# SHDN-S04-V00-ShutdownRelay.net
KiCad netlist of a schematic drawn in Altium Designer
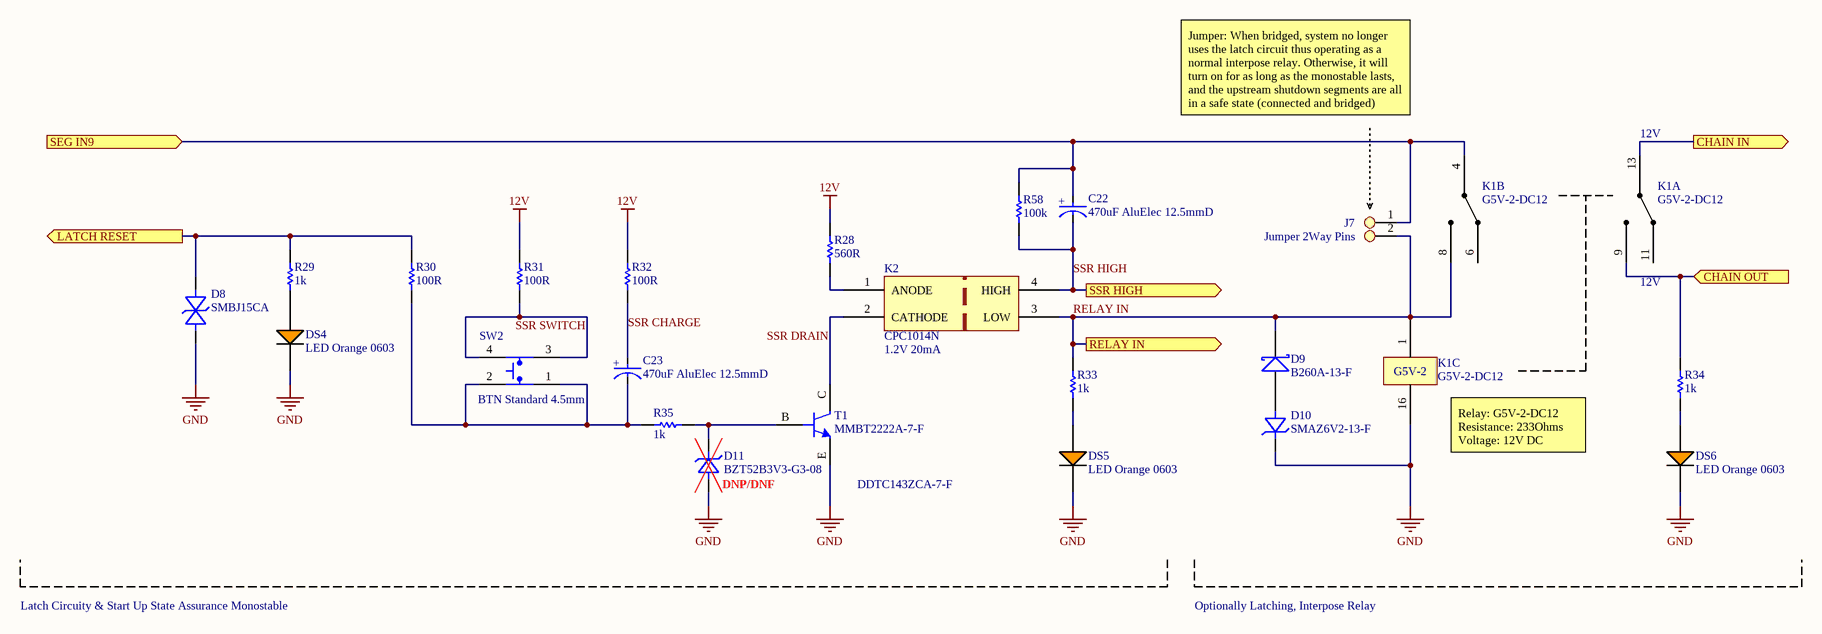
[diagram p0: SHDN-S04-V00-ShutdownRelay.SchDoc]

(export (version "E")
  (design (tool "Eeschema 10.0.6"))
  (components
    (comp (ref "C22")
      (value "470uF AluElec 12.5mmD")
      (footprint "CAL_ALU_12.5mmD_20mmL")
      (description "Capacitor, AluElec, SMD, 470F, 50V, 20%, AluElec, 12.5mmD")
      (libsource (lib "StandardCapacitors") (part "470uF 50V 20% AluElec 12.5mmD"))
    )
    (comp (ref "C23")
      (value "470uF AluElec 12.5mmD")
      (footprint "CAL_ALU_12.5mmD_20mmL")
      (description "Capacitor, AluElec, SMD, 470F, 50V, 20%, AluElec, 12.5mmD")
      (libsource (lib "StandardCapacitors") (part "470uF 50V 20% AluElec 12.5mmD"))
    )
    (comp (ref "D8")
      (value "SMBJ15CA")
      (footprint "SMB")
      (description "Diode, SMD, TVS Diode, 15V 24.4V, DO214AA/SMB")
      (libsource (lib "QUTMS_DiodeLibrary") (part "SMBJ15CA"))
    )
    (comp (ref "D9")
      (value "B260A-13-F")
      (footprint "SMA")
      (description "Diode, Schottky Barrier Rectifier, 60 V, 2 A, B260A-13-F")
      (libsource (lib "QUTMS_DiodeLibrary") (part "B260A-13-F"))
    )
    (comp (ref "D10")
      (value "SMAZ6V2-13-F")
      (footprint "SMA")
      (description "Zener Diode 6.2V 1W ±5% Surface Mount SMA")
      (fields (field (name "MANUFACTURER") "Generic") (field (name "MPN") "5V6 500mW SMA"))
      (libsource (lib "QUTMS_DiodeLibrary") (part "SMAZ6V2-13-F"))
    )
    (comp (ref "D11")
      (value "BZT52B3V3-G3-08")
      (footprint "SOD123")
      (description "Diode, SMD, Zenner, 3.3V, 2%, 410mW, SOD-123")
      (libsource (lib "QUTMS_DiodeLibrary") (part "BZT52B3V3-G3-08"))
    )
    (comp (ref "DS4")
      (value "LED Orange 0603")
      (footprint "LED ORANGE 0603")
      (libsource (lib "QUTMS_LEDLibrary") (part "LED Orange 0603"))
    )
    (comp (ref "DS5")
      (value "LED Orange 0603")
      (footprint "LED ORANGE 0603")
      (libsource (lib "QUTMS_LEDLibrary") (part "LED Orange 0603"))
    )
    (comp (ref "DS6")
      (value "LED Orange 0603")
      (footprint "LED ORANGE 0603")
      (libsource (lib "QUTMS_LEDLibrary") (part "LED Orange 0603"))
    )
    (comp (ref "J7")
      (value "Jumper 2Way Pins")
      (footprint "Jumper_2Way_Pin")
      (description "Jumper 2Way Side Pins")
      (libsource (lib "QUTMS_JumperLibrary") (part "Jumper 2Way Side Pins"))
    )
    (comp (ref "K1")
      (value "G5V-2-DC12")
      (footprint "G5V-2")
      (description "General Purpose Relay DPDT (2 Form C) Through Hole, 12V, 2A")
      (libsource (lib "QUTMS_RelayLibrary") (part "G5V-2-DC12"))
    )
    (comp (ref "K2")
      (value "CPC1014N")
      (footprint "CPC1014N")
      (description "Solid State SPST-NO (1 Form A) 4-SOP (0.150\", 3.81mm)")
      (libsource (lib "QUTMS_RelayLibrary") (part "CPC1014N"))
    )
    (comp (ref "R28")
      (value "560R")
      (footprint "Res_ThinFilm_0603")
      (description "Resistor, SMD, 560R, 0.1W, 5%, 0603")
      (libsource (lib "StandardResistors") (part "560R 5% 0603"))
    )
    (comp (ref "R29")
      (value "1k")
      (footprint "Res_ThinFilm_0603")
      (description "Resistor, SMD, 1k, 0.1W, 5%, 0603")
      (libsource (lib "StandardResistors") (part "1k 5% 0603"))
    )
    (comp (ref "R30")
      (value "100R")
      (footprint "Res_ThinFilm_0603")
      (description "Resistor, SMD, 100R, 0.1W, 5%, 0603")
      (libsource (lib "StandardResistors") (part "100R 5%, 0603"))
    )
    (comp (ref "R31")
      (value "100R")
      (footprint "Res_ThinFilm_0603")
      (description "Resistor, SMD, 100R, 0.1W, 5%, 0603")
      (libsource (lib "StandardResistors") (part "100R 5%, 0603"))
    )
    (comp (ref "R32")
      (value "100R")
      (footprint "Res_ThinFilm_0603")
      (description "Resistor, SMD, 100R, 0.1W, 5%, 0603")
      (libsource (lib "StandardResistors") (part "100R 5%, 0603"))
    )
    (comp (ref "R33")
      (value "1k")
      (footprint "Res_ThinFilm_0603")
      (description "Resistor, SMD, 1k, 0.1W, 5%, 0603")
      (libsource (lib "StandardResistors") (part "1k 5% 0603"))
    )
    (comp (ref "R34")
      (value "1k")
      (footprint "Res_ThinFilm_0603")
      (description "Resistor, SMD, 1k, 0.1W, 5%, 0603")
      (libsource (lib "StandardResistors") (part "1k 5% 0603"))
    )
    (comp (ref "R35")
      (value "1k")
      (footprint "Res_ThinFilm_0603")
      (description "Resistor, SMD, 1k, 0.1W, 5%, 0603")
      (libsource (lib "StandardResistors") (part "1k 5% 0603"))
    )
    (comp (ref "R58")
      (value "100k")
      (footprint "Res_ThinFilm_0603")
      (description "Resistor, SMD, 100k, 0.1W, 5%, 0603")
      (libsource (lib "StandardResistors") (part "100k 5%, 0603"))
    )
    (comp (ref "SW2")
      (value "BTN Standard 4.5mm")
      (footprint "BTN STANDARD 4.5mm X 4.5mm")
      (description "Standard 4.5mm X 4.5mm momentary button")
      (libsource (lib "QUTMS_SwitchLibrary") (part "BTN Standard 4.5mm"))
    )
    (comp (ref "T1")
      (value "MMBT2222A-7-F")
      (footprint "SOT23-3 - Transistor")
      (description "Bipolar (BJT) Transistor NPN 40V 600mA 300MHz 310mW Surface Mount SOT-23-3")
      (libsource (lib "QUTMS_MOSFETLibrary") (part "MMBT2222A-7-F"))
    )
  )
  (nets
    (net (code "1") (name "/CHAIN IN") (class "Default")
      (node (ref "K1") (pin "13") (pinfunction "13_13") (pintype "passive"))
    )
    (net (code "2") (name "/CHAIN OUT") (class "Default")
      (node (ref "K1") (pin "9") (pinfunction "9_9") (pintype "passive"))
      (node (ref "R34") (pin "2") (pinfunction "2_2") (pintype "passive"))
    )
    (net (code "3") (name "/LATCH RESET") (class "Default")
      (node (ref "D8") (pin "K") (pinfunction "Cathode_K") (pintype "passive"))
      (node (ref "R29") (pin "2") (pinfunction "2_2") (pintype "passive"))
      (node (ref "R30") (pin "2") (pinfunction "2_2") (pintype "passive"))
    )
    (net (code "4") (name "/RELAY IN") (class "Default")
      (node (ref "D9") (pin "K") (pinfunction "K_K") (pintype "passive"))
      (node (ref "J7") (pin "2") (pinfunction "2_2") (pintype "passive"))
      (node (ref "K1") (pin "1") (pinfunction "1_1") (pintype "passive"))
      (node (ref "K1") (pin "8") (pinfunction "8_8") (pintype "passive"))
      (node (ref "K2") (pin "3") (pinfunction "LOW_3") (pintype "passive"))
      (node (ref "R33") (pin "2") (pinfunction "2_2") (pintype "passive"))
    )
    (net (code "5") (name "/SEG IN9") (class "Default")
      (node (ref "C22") (pin "A") (pinfunction "A_A") (pintype "passive"))
      (node (ref "J7") (pin "1") (pinfunction "1_1") (pintype "passive"))
      (node (ref "K1") (pin "4") (pinfunction "4_4") (pintype "passive"))
      (node (ref "R58") (pin "2") (pinfunction "2_2") (pintype "passive"))
    )
    (net (code "6") (name "/SSR CHARGE") (class "Default")
      (node (ref "C23") (pin "A") (pinfunction "A_A") (pintype "passive"))
      (node (ref "R32") (pin "1") (pinfunction "1_1") (pintype "passive"))
    )
    (net (code "7") (name "/SSR DRAIN") (class "Default")
      (node (ref "K2") (pin "2") (pinfunction "CATHODE_2") (pintype "passive"))
      (node (ref "T1") (pin "C") (pinfunction "C_C") (pintype "passive"))
    )
    (net (code "8") (name "/SSR HIGH") (class "Default")
      (node (ref "C22") (pin "K") (pinfunction "K_K") (pintype "passive"))
      (node (ref "K2") (pin "4") (pinfunction "HIGH_4") (pintype "passive"))
      (node (ref "R58") (pin "1") (pinfunction "1_1") (pintype "passive"))
    )
    (net (code "9") (name "/SSR SWITCH") (class "Default")
      (node (ref "R31") (pin "1") (pinfunction "1_1") (pintype "passive"))
      (node (ref "SW2") (pin "3") (pinfunction "3_3") (pintype "passive"))
      (node (ref "SW2") (pin "4") (pinfunction "4_4") (pintype "passive"))
    )
    (net (code "10") (name "12V") (class "Default")
      (node (ref "R28") (pin "1") (pinfunction "1_1") (pintype "passive"))
      (node (ref "R31") (pin "2") (pinfunction "2_2") (pintype "passive"))
      (node (ref "R32") (pin "2") (pinfunction "2_2") (pintype "passive"))
    )
    (net (code "11") (name "GND") (class "Default")
      (node (ref "D10") (pin "K") (pinfunction "Cathode_K") (pintype "passive"))
      (node (ref "D11") (pin "A") (pinfunction "Anode_A") (pintype "passive"))
      (node (ref "D8") (pin "A") (pinfunction "Anode_A") (pintype "passive"))
      (node (ref "DS4") (pin "2") (pinfunction "C_2") (pintype "passive"))
      (node (ref "DS5") (pin "2") (pinfunction "C_2") (pintype "passive"))
      (node (ref "DS6") (pin "2") (pinfunction "C_2") (pintype "passive"))
      (node (ref "K1") (pin "16") (pinfunction "16_16") (pintype "passive"))
      (node (ref "T1") (pin "E") (pinfunction "E_E") (pintype "passive"))
    )
    (net (code "12") (name "Net-(C23-PadK)") (class "Default")
      (node (ref "C23") (pin "K") (pinfunction "K_K") (pintype "passive"))
      (node (ref "R30") (pin "1") (pinfunction "1_1") (pintype "passive"))
      (node (ref "R35") (pin "1") (pinfunction "1_1") (pintype "passive"))
      (node (ref "SW2") (pin "1") (pinfunction "1_1") (pintype "passive"))
      (node (ref "SW2") (pin "2") (pinfunction "2_2") (pintype "passive"))
    )
    (net (code "13") (name "Net-(D10-Anode)") (class "Default")
      (node (ref "D10") (pin "A") (pinfunction "Anode_A") (pintype "passive"))
      (node (ref "D9") (pin "A") (pinfunction "A_A") (pintype "passive"))
    )
    (net (code "14") (name "Net-(D11-Cathode)") (class "Default")
      (node (ref "D11") (pin "K") (pinfunction "Cathode_K") (pintype "passive"))
      (node (ref "R35") (pin "2") (pinfunction "2_2") (pintype "passive"))
      (node (ref "T1") (pin "B") (pinfunction "B_B") (pintype "passive"))
    )
    (net (code "15") (name "Net-(DS4-A)") (class "Default")
      (node (ref "DS4") (pin "1") (pinfunction "A_1") (pintype "passive"))
      (node (ref "R29") (pin "1") (pinfunction "1_1") (pintype "passive"))
    )
    (net (code "16") (name "Net-(DS5-A)") (class "Default")
      (node (ref "DS5") (pin "1") (pinfunction "A_1") (pintype "passive"))
      (node (ref "R33") (pin "1") (pinfunction "1_1") (pintype "passive"))
    )
    (net (code "17") (name "Net-(DS6-A)") (class "Default")
      (node (ref "DS6") (pin "1") (pinfunction "A_1") (pintype "passive"))
      (node (ref "R34") (pin "1") (pinfunction "1_1") (pintype "passive"))
    )
    (net (code "18") (name "Net-(K2-ANODE)") (class "Default")
      (node (ref "K2") (pin "1") (pinfunction "ANODE_1") (pintype "passive"))
      (node (ref "R28") (pin "2") (pinfunction "2_2") (pintype "passive"))
    )
    (net (code "19") (name "unconnected-(K1-Pad6)") (class "Default")
      (node (ref "K1") (pin "6") (pinfunction "6_6") (pintype "passive"))
    )
    (net (code "20") (name "unconnected-(K1-Pad11)") (class "Default")
      (node (ref "K1") (pin "11") (pinfunction "11_11") (pintype "passive"))
    )
  )
)
